# lidar2.net
KiCad netlist of a schematic drawn in EAGLE
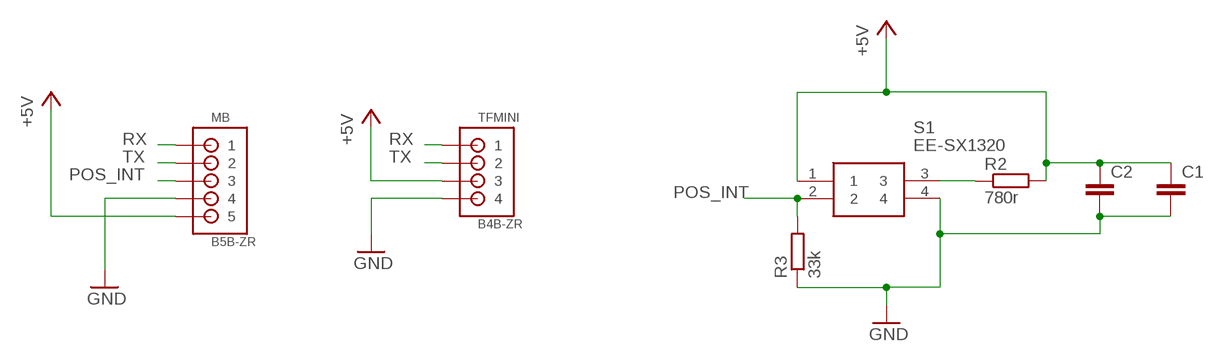
[diagram p0: schematic, sheet 1]

(export (version "E")
  (design (tool "Eeschema 10.0.6"))
  (components
    (comp (ref "C1")
      (value "C-EUC1206")
      (footprint "eagle-import:C1206")
      (libsource (lib "eagle-import") (part "C-EUC1206"))
    )
    (comp (ref "C2")
      (value "C-EUC0805")
      (footprint "eagle-import:C0805")
      (libsource (lib "eagle-import") (part "C-EUC0805"))
    )
    (comp (ref "MB")
      (value "B5B-ZR")
      (footprint "eagle-import:B5B-ZR")
      (libsource (lib "eagle-import") (part "B5B-ZR"))
    )
    (comp (ref "R2")
      (value "780r")
      (footprint "eagle-import:R0603")
      (libsource (lib "eagle-import") (part "R-EU_R0603"))
    )
    (comp (ref "R3")
      (value "33k")
      (footprint "eagle-import:R0603")
      (libsource (lib "eagle-import") (part "R-EU_R0603"))
    )
    (comp (ref "S1")
      (value "EE-SX1320")
      (footprint "eagle-import:EE-SX1320")
      (fields (field (name "MOUSER_PART_NUMBER") "653-EESX1320"))
      (libsource (lib "eagle-import") (part "EE-SX1320"))
    )
    (comp (ref "TFMINI")
      (value "B4B-ZR")
      (footprint "eagle-import:B4B-ZR")
      (libsource (lib "eagle-import") (part "B4B-ZR"))
    )
  )
  (nets
    (net (code "1") (name "+5V") (class "Default")
      (node (ref "C1") (pin "1") (pinfunction "1_1") (pintype "passive"))
      (node (ref "C2") (pin "1") (pinfunction "1_1") (pintype "passive"))
      (node (ref "MB") (pin "5") (pinfunction "5_5") (pintype "bidirectional"))
      (node (ref "R2") (pin "2") (pinfunction "2_2") (pintype "passive"))
      (node (ref "S1") (pin "1") (pinfunction "1_1") (pintype "bidirectional"))
      (node (ref "TFMINI") (pin "3") (pinfunction "3_3") (pintype "bidirectional"))
    )
    (net (code "2") (name "/POS_INT") (class "Default")
      (node (ref "MB") (pin "3") (pinfunction "3_3") (pintype "bidirectional"))
      (node (ref "R3") (pin "2") (pinfunction "2_2") (pintype "passive"))
      (node (ref "S1") (pin "2") (pinfunction "2_2") (pintype "bidirectional"))
    )
    (net (code "3") (name "/RX") (class "Default")
      (node (ref "MB") (pin "1") (pinfunction "1_1") (pintype "bidirectional"))
      (node (ref "TFMINI") (pin "1") (pinfunction "1_1") (pintype "bidirectional"))
    )
    (net (code "4") (name "/TX") (class "Default")
      (node (ref "MB") (pin "2") (pinfunction "2_2") (pintype "bidirectional"))
      (node (ref "TFMINI") (pin "2") (pinfunction "2_2") (pintype "bidirectional"))
    )
    (net (code "5") (name "GND") (class "Default")
      (node (ref "C1") (pin "2") (pinfunction "2_2") (pintype "passive"))
      (node (ref "C2") (pin "2") (pinfunction "2_2") (pintype "passive"))
      (node (ref "MB") (pin "4") (pinfunction "4_4") (pintype "bidirectional"))
      (node (ref "R3") (pin "1") (pinfunction "1_1") (pintype "passive"))
      (node (ref "S1") (pin "4") (pinfunction "4_4") (pintype "bidirectional"))
      (node (ref "TFMINI") (pin "4") (pinfunction "4_4") (pintype "bidirectional"))
    )
    (net (code "6") (name "Net-(R2-Pad1)") (class "Default")
      (node (ref "R2") (pin "1") (pinfunction "1_1") (pintype "passive"))
      (node (ref "S1") (pin "3") (pinfunction "3_3") (pintype "bidirectional"))
    )
  )
)
